# aa_battery_lado_a_lado.net
KiCad netlist of a schematic drawn in EAGLE
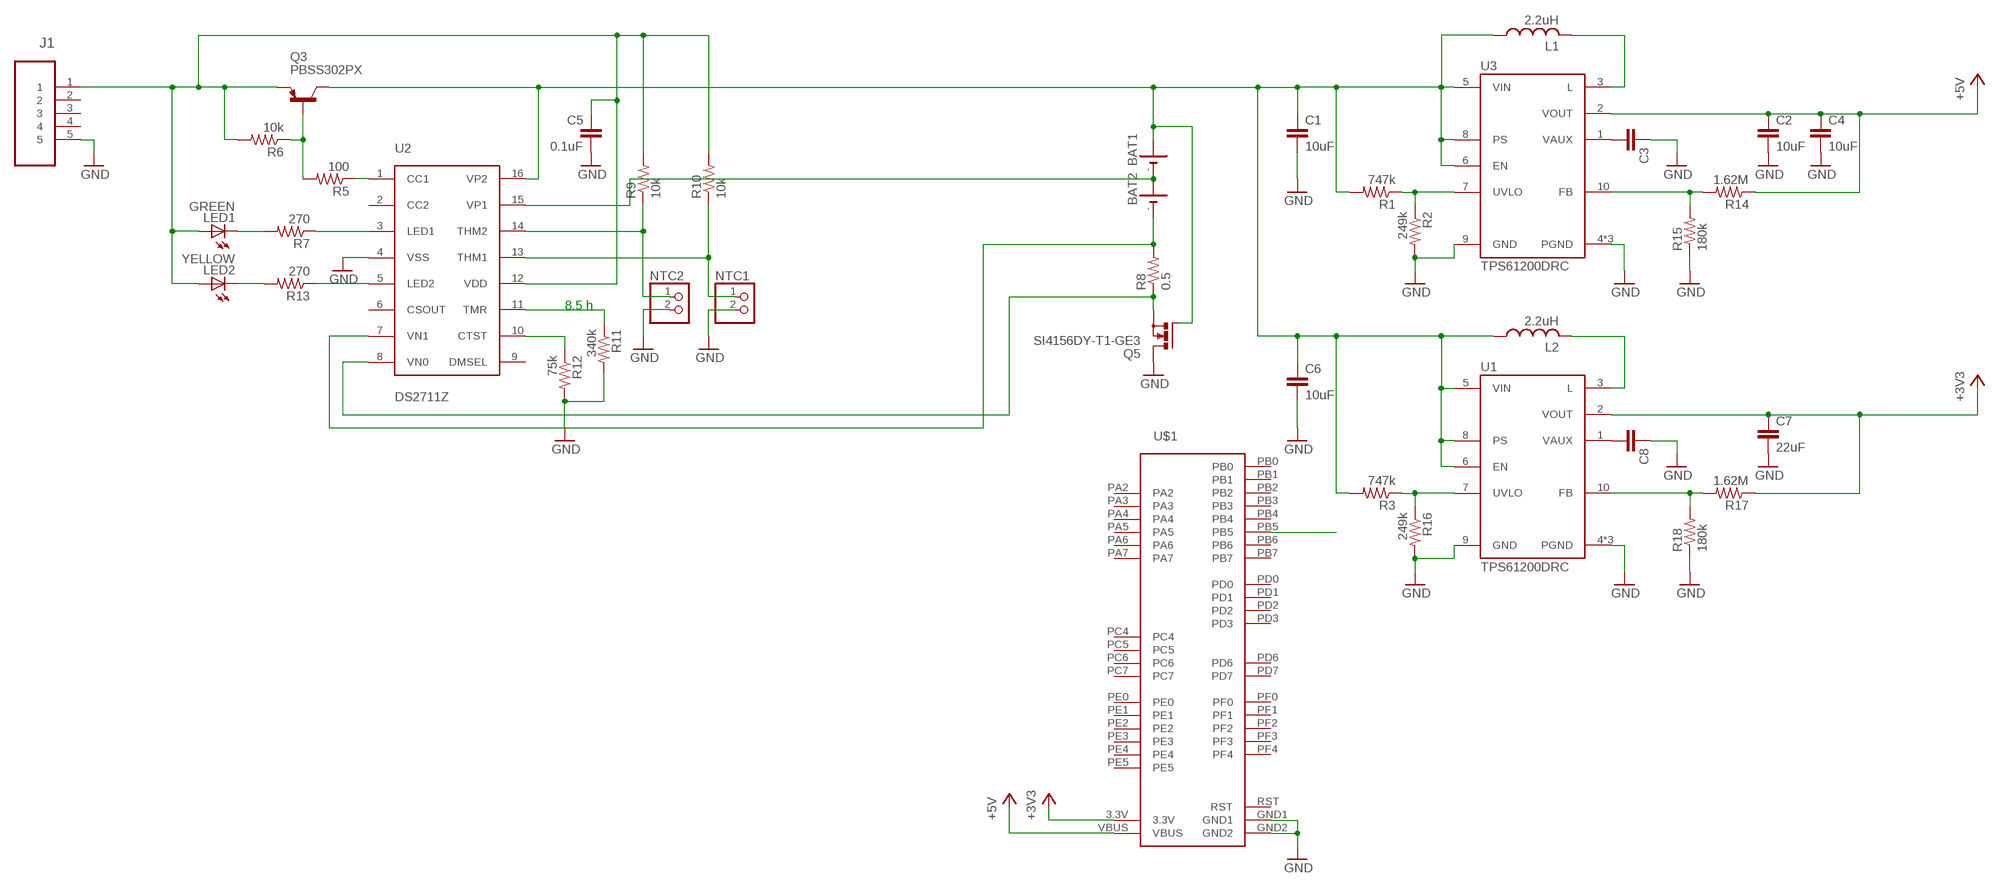
[diagram p0: schematic, sheet 1]

(export (version "E")
  (design (tool "Eeschema 10.0.6"))
  (components
    (comp (ref "BAT1")
      (value "AA-SNGLKEYSTONE2460")
      (footprint "eagle-import:KEYSTONE2460")
      (libsource (lib "eagle-import") (part "AA-SNGLKEYSTONE2460"))
    )
    (comp (ref "BAT2")
      (value "AA-SNGLKEYSTONE2460")
      (footprint "eagle-import:KEYSTONE2460")
      (libsource (lib "eagle-import") (part "AA-SNGLKEYSTONE2460"))
    )
    (comp (ref "C1")
      (value "10uF")
      (footprint "eagle-import:C0805")
      (libsource (lib "eagle-import") (part "C-EUC0805"))
    )
    (comp (ref "C2")
      (value "10uF")
      (footprint "eagle-import:C0805")
      (libsource (lib "eagle-import") (part "C-EUC0805"))
    )
    (comp (ref "C3")
      (value "C-EUC0805")
      (footprint "eagle-import:C0805")
      (libsource (lib "eagle-import") (part "C-EUC0805"))
    )
    (comp (ref "C4")
      (value "10uF")
      (footprint "eagle-import:C0805")
      (libsource (lib "eagle-import") (part "C-EUC0805"))
    )
    (comp (ref "C5")
      (value "0.1uF")
      (footprint "eagle-import:C0805")
      (libsource (lib "eagle-import") (part "C-EUC0805"))
    )
    (comp (ref "C6")
      (value "10uF")
      (footprint "eagle-import:C0805")
      (libsource (lib "eagle-import") (part "C-EUC0805"))
    )
    (comp (ref "C7")
      (value "22uF")
      (footprint "eagle-import:C0805")
      (libsource (lib "eagle-import") (part "C-EUC0805"))
    )
    (comp (ref "C8")
      (value "C-EUC0603")
      (footprint "eagle-import:C0603")
      (libsource (lib "eagle-import") (part "C-EUC0603"))
    )
    (comp (ref "J1")
      (value "47346-0001")
      (footprint "eagle-import:MOLEX_47346-0001")
      (libsource (lib "eagle-import") (part "47346-0001"))
    )
    (comp (ref "L1")
      (value "2.2uH")
      (footprint "eagle-import:XAL4040")
      (libsource (lib "eagle-import") (part "L-USXAL4040"))
    )
    (comp (ref "L2")
      (value "2.2uH")
      (footprint "eagle-import:XAL4040")
      (libsource (lib "eagle-import") (part "L-USXAL4040"))
    )
    (comp (ref "LED1")
      (value "GREEN")
      (footprint "eagle-import:SML1206")
      (libsource (lib "eagle-import") (part "LEDSML1206"))
    )
    (comp (ref "LED2")
      (value "YELLOW")
      (footprint "eagle-import:SML1206")
      (libsource (lib "eagle-import") (part "LEDSML1206"))
    )
    (comp (ref "NTC1")
      (value "PINHD-1X2")
      (footprint "eagle-import:1X02")
      (libsource (lib "eagle-import") (part "PINHD-1X2"))
    )
    (comp (ref "NTC2")
      (value "PINHD-1X2")
      (footprint "eagle-import:1X02")
      (libsource (lib "eagle-import") (part "PINHD-1X2"))
    )
    (comp (ref "Q3")
      (value "PBSS302PX")
      (footprint "eagle-import:SOT89-BCE")
      (libsource (lib "eagle-import") (part "-PNP-SOT98-BCEBF621"))
    )
    (comp (ref "Q5")
      (value "SI4156DY-T1-GE3")
      (footprint "eagle-import:SO-08")
      (libsource (lib "eagle-import") (part "N-MOSFET-SO8S"))
    )
    (comp (ref "R1")
      (value "747k")
      (footprint "eagle-import:R0603")
      (libsource (lib "eagle-import") (part "R-US_R0603"))
    )
    (comp (ref "R2")
      (value "249k")
      (footprint "eagle-import:R0603")
      (libsource (lib "eagle-import") (part "R-US_R0603"))
    )
    (comp (ref "R3")
      (value "747k")
      (footprint "eagle-import:R0603")
      (libsource (lib "eagle-import") (part "R-US_R0603"))
    )
    (comp (ref "R5")
      (value "100")
      (footprint "eagle-import:R0805")
      (libsource (lib "eagle-import") (part "R-US_R0805"))
    )
    (comp (ref "R6")
      (value "10k")
      (footprint "eagle-import:R0805")
      (libsource (lib "eagle-import") (part "R-US_R0805"))
    )
    (comp (ref "R7")
      (value "270")
      (footprint "eagle-import:R0805")
      (libsource (lib "eagle-import") (part "R-US_R0805"))
    )
    (comp (ref "R8")
      (value "0.5")
      (footprint "eagle-import:R0805")
      (libsource (lib "eagle-import") (part "R-US_R0805"))
    )
    (comp (ref "R9")
      (value "10k")
      (footprint "eagle-import:R0805")
      (libsource (lib "eagle-import") (part "R-US_R0805"))
    )
    (comp (ref "R10")
      (value "10k")
      (footprint "eagle-import:R0805")
      (libsource (lib "eagle-import") (part "R-US_R0805"))
    )
    (comp (ref "R11")
      (value "340k")
      (footprint "eagle-import:R0805")
      (libsource (lib "eagle-import") (part "R-US_R0805"))
    )
    (comp (ref "R12")
      (value "75k")
      (footprint "eagle-import:R0805")
      (libsource (lib "eagle-import") (part "R-US_R0805"))
    )
    (comp (ref "R13")
      (value "270")
      (footprint "eagle-import:R0805")
      (libsource (lib "eagle-import") (part "R-US_R0805"))
    )
    (comp (ref "R14")
      (value "1.62M")
      (footprint "eagle-import:R0603")
      (libsource (lib "eagle-import") (part "R-US_R0603"))
    )
    (comp (ref "R15")
      (value "180k")
      (footprint "eagle-import:R0603")
      (libsource (lib "eagle-import") (part "R-US_R0603"))
    )
    (comp (ref "R16")
      (value "249k")
      (footprint "eagle-import:R0603")
      (libsource (lib "eagle-import") (part "R-US_R0603"))
    )
    (comp (ref "R17")
      (value "1.62M")
      (footprint "eagle-import:R0603")
      (libsource (lib "eagle-import") (part "R-US_R0603"))
    )
    (comp (ref "R18")
      (value "180k")
      (footprint "eagle-import:R0603")
      (libsource (lib "eagle-import") (part "R-US_R0603"))
    )
    (comp (ref "U$1")
      (value "STELLARIS-LAUNCHPADSTELLARIS-LAUNCHPAD-XL-HALF-LENGTH")
      (footprint "eagle-import:LAUNCHPAD-XL-HALF-LENGTH")
      (libsource (lib "eagle-import") (part "STELLARIS-LAUNCHPADSTELLARIS-LAUNCHPAD-XL-HALF-LENGTH"))
    )
    (comp (ref "U1")
      (value "TPS61200DRC")
      (footprint "eagle-import:DRC10_2P4X1P65")
      (libsource (lib "eagle-import") (part "TPS61200DRC"))
    )
    (comp (ref "U2")
      (value "DS2711Z")
      (footprint "eagle-import:SO16")
      (libsource (lib "eagle-import") (part "DS2711Z"))
    )
    (comp (ref "U3")
      (value "TPS61200DRC")
      (footprint "eagle-import:DRC10_2P4X1P65")
      (libsource (lib "eagle-import") (part "TPS61200DRC"))
    )
  )
  (nets
    (net (code "1") (name "+3V3") (class "Default")
      (node (ref "C7") (pin "1") (pinfunction "1_1") (pintype "passive"))
      (node (ref "R17") (pin "1") (pinfunction "1_1") (pintype "passive"))
      (node (ref "U$1") (pin "3.3V") (pinfunction "3.3V_3.3V") (pintype "power_in"))
      (node (ref "U1") (pin "2") (pinfunction "VOUT_2") (pintype "bidirectional"))
    )
    (net (code "2") (name "+5V") (class "Default")
      (node (ref "C2") (pin "1") (pinfunction "1_1") (pintype "passive"))
      (node (ref "C4") (pin "1") (pinfunction "1_1") (pintype "passive"))
      (node (ref "R14") (pin "1") (pinfunction "1_1") (pintype "passive"))
      (node (ref "U$1") (pin "VBUS") (pinfunction "VBUS_VBUS") (pintype "power_in"))
      (node (ref "U3") (pin "2") (pinfunction "VOUT_2") (pintype "bidirectional"))
    )
    (net (code "3") (name "/RST") (class "Default")
      (node (ref "U$1") (pin "RST") (pinfunction "RST_RST") (pintype "power_in"))
    )
    (net (code "4") (name "GND") (class "Default")
      (node (ref "C1") (pin "2") (pinfunction "2_2") (pintype "passive"))
      (node (ref "C2") (pin "2") (pinfunction "2_2") (pintype "passive"))
      (node (ref "C3") (pin "1") (pinfunction "1_1") (pintype "passive"))
      (node (ref "C4") (pin "2") (pinfunction "2_2") (pintype "passive"))
      (node (ref "C5") (pin "2") (pinfunction "2_2") (pintype "passive"))
      (node (ref "C6") (pin "2") (pinfunction "2_2") (pintype "passive"))
      (node (ref "C7") (pin "2") (pinfunction "2_2") (pintype "passive"))
      (node (ref "C8") (pin "1") (pinfunction "1_1") (pintype "passive"))
      (node (ref "J1") (pin "5") (pinfunction "5_5") (pintype "input"))
      (node (ref "NTC1") (pin "2") (pinfunction "2_2") (pintype "passive"))
      (node (ref "NTC2") (pin "2") (pinfunction "2_2") (pintype "passive"))
      (node (ref "Q5") (pin "5") (pinfunction "D_5") (pintype "passive"))
      (node (ref "Q5") (pin "6") (pinfunction "D_6") (pintype "passive"))
      (node (ref "Q5") (pin "7") (pinfunction "D_7") (pintype "passive"))
      (node (ref "Q5") (pin "8") (pinfunction "D_8") (pintype "passive"))
      (node (ref "R11") (pin "2") (pinfunction "2_2") (pintype "passive"))
      (node (ref "R12") (pin "2") (pinfunction "2_2") (pintype "passive"))
      (node (ref "R15") (pin "1") (pinfunction "1_1") (pintype "passive"))
      (node (ref "R16") (pin "2") (pinfunction "2_2") (pintype "passive"))
      (node (ref "R18") (pin "1") (pinfunction "1_1") (pintype "passive"))
      (node (ref "R2") (pin "2") (pinfunction "2_2") (pintype "passive"))
      (node (ref "U$1") (pin "GND1") (pinfunction "GND1_GND1") (pintype "bidirectional"))
      (node (ref "U$1") (pin "GND2") (pinfunction "GND2_GND2") (pintype "power_in"))
      (node (ref "U1") (pin "11") (pinfunction "PGND_11") (pintype "bidirectional"))
      (node (ref "U1") (pin "12") (pinfunction "PGND_12") (pintype "bidirectional"))
      (node (ref "U1") (pin "4") (pinfunction "PGND_4") (pintype "bidirectional"))
      (node (ref "U1") (pin "9") (pinfunction "GND_9") (pintype "bidirectional"))
      (node (ref "U2") (pin "4") (pinfunction "VSS_4") (pintype "bidirectional"))
      (node (ref "U3") (pin "11") (pinfunction "PGND_11") (pintype "bidirectional"))
      (node (ref "U3") (pin "12") (pinfunction "PGND_12") (pintype "bidirectional"))
      (node (ref "U3") (pin "4") (pinfunction "PGND_4") (pintype "bidirectional"))
      (node (ref "U3") (pin "9") (pinfunction "GND_9") (pintype "bidirectional"))
    )
    (net (code "5") (name "Net-(LED1-PadC)") (class "Default")
      (node (ref "LED1") (pin "C") (pinfunction "C_C") (pintype "passive"))
      (node (ref "R7") (pin "2") (pinfunction "2_2") (pintype "passive"))
    )
    (net (code "6") (name "Net-(LED2-PadC)") (class "Default")
      (node (ref "LED2") (pin "C") (pinfunction "C_C") (pintype "passive"))
      (node (ref "R13") (pin "2") (pinfunction "2_2") (pintype "passive"))
    )
    (net (code "7") (name "Net-(Q3-PadB)") (class "Default")
      (node (ref "Q3") (pin "B") (pinfunction "B_B") (pintype "passive"))
      (node (ref "R5") (pin "2") (pinfunction "2_2") (pintype "passive"))
      (node (ref "R6") (pin "1") (pinfunction "1_1") (pintype "passive"))
    )
    (net (code "8") (name "Net-(Q5-G)") (class "Default")
      (node (ref "BAT1") (pin "+") (pinfunction "+_+") (pintype "passive"))
      (node (ref "C1") (pin "1") (pinfunction "1_1") (pintype "passive"))
      (node (ref "C6") (pin "1") (pinfunction "1_1") (pintype "passive"))
      (node (ref "L1") (pin "1") (pinfunction "1_1") (pintype "passive"))
      (node (ref "L2") (pin "1") (pinfunction "1_1") (pintype "passive"))
      (node (ref "Q3") (pin "C") (pinfunction "C_C") (pintype "passive"))
      (node (ref "Q3") (pin "C@1") (pinfunction "C_C@1") (pintype "passive"))
      (node (ref "Q5") (pin "4") (pinfunction "G_4") (pintype "passive"))
      (node (ref "R1") (pin "2") (pinfunction "2_2") (pintype "passive"))
      (node (ref "R3") (pin "2") (pinfunction "2_2") (pintype "passive"))
      (node (ref "U1") (pin "5") (pinfunction "VIN_5") (pintype "bidirectional"))
      (node (ref "U1") (pin "6") (pinfunction "EN_6") (pintype "bidirectional"))
      (node (ref "U1") (pin "8") (pinfunction "PS_8") (pintype "bidirectional"))
      (node (ref "U2") (pin "16") (pinfunction "VP2_16") (pintype "bidirectional"))
      (node (ref "U3") (pin "5") (pinfunction "VIN_5") (pintype "bidirectional"))
      (node (ref "U3") (pin "6") (pinfunction "EN_6") (pintype "bidirectional"))
      (node (ref "U3") (pin "8") (pinfunction "PS_8") (pintype "bidirectional"))
    )
    (net (code "9") (name "Net-(U1-FB)") (class "Default")
      (node (ref "R17") (pin "2") (pinfunction "2_2") (pintype "passive"))
      (node (ref "R18") (pin "2") (pinfunction "2_2") (pintype "passive"))
      (node (ref "U1") (pin "10") (pinfunction "FB_10") (pintype "bidirectional"))
    )
    (net (code "10") (name "Net-(U1-L)") (class "Default")
      (node (ref "L2") (pin "2") (pinfunction "2_2") (pintype "passive"))
      (node (ref "U1") (pin "3") (pinfunction "L_3") (pintype "bidirectional"))
    )
    (net (code "11") (name "Net-(U1-UVLO)") (class "Default")
      (node (ref "R16") (pin "1") (pinfunction "1_1") (pintype "passive"))
      (node (ref "R3") (pin "1") (pinfunction "1_1") (pintype "passive"))
      (node (ref "U1") (pin "7") (pinfunction "UVLO_7") (pintype "bidirectional"))
    )
    (net (code "12") (name "Net-(U1-VAUX)") (class "Default")
      (node (ref "C8") (pin "2") (pinfunction "2_2") (pintype "passive"))
      (node (ref "U1") (pin "1") (pinfunction "VAUX_1") (pintype "bidirectional"))
    )
    (net (code "13") (name "Net-(U2-CC1)") (class "Default")
      (node (ref "R5") (pin "1") (pinfunction "1_1") (pintype "passive"))
      (node (ref "U2") (pin "1") (pinfunction "CC1_1") (pintype "bidirectional"))
    )
    (net (code "14") (name "Net-(U2-CTST)") (class "Default")
      (node (ref "R12") (pin "1") (pinfunction "1_1") (pintype "passive"))
      (node (ref "U2") (pin "10") (pinfunction "CTST_10") (pintype "bidirectional"))
    )
    (net (code "15") (name "Net-(U2-LED1)") (class "Default")
      (node (ref "R7") (pin "1") (pinfunction "1_1") (pintype "passive"))
      (node (ref "U2") (pin "3") (pinfunction "LED1_3") (pintype "bidirectional"))
    )
    (net (code "16") (name "Net-(U2-LED2)") (class "Default")
      (node (ref "R13") (pin "1") (pinfunction "1_1") (pintype "passive"))
      (node (ref "U2") (pin "5") (pinfunction "LED2_5") (pintype "bidirectional"))
    )
    (net (code "17") (name "Net-(U2-THM1)") (class "Default")
      (node (ref "NTC1") (pin "1") (pinfunction "1_1") (pintype "passive"))
      (node (ref "R10") (pin "1") (pinfunction "1_1") (pintype "passive"))
      (node (ref "U2") (pin "13") (pinfunction "THM1_13") (pintype "bidirectional"))
    )
    (net (code "18") (name "Net-(U2-THM2)") (class "Default")
      (node (ref "NTC2") (pin "1") (pinfunction "1_1") (pintype "passive"))
      (node (ref "R9") (pin "1") (pinfunction "1_1") (pintype "passive"))
      (node (ref "U2") (pin "14") (pinfunction "THM2_14") (pintype "bidirectional"))
    )
    (net (code "19") (name "Net-(U2-TMR)") (class "Default")
      (node (ref "R11") (pin "1") (pinfunction "1_1") (pintype "passive"))
      (node (ref "U2") (pin "11") (pinfunction "TMR_11") (pintype "bidirectional"))
    )
    (net (code "20") (name "Net-(U2-VDD)") (class "Default")
      (node (ref "C5") (pin "1") (pinfunction "1_1") (pintype "passive"))
      (node (ref "J1") (pin "1") (pinfunction "1_1") (pintype "input"))
      (node (ref "LED1") (pin "A") (pinfunction "A_A") (pintype "passive"))
      (node (ref "LED2") (pin "A") (pinfunction "A_A") (pintype "passive"))
      (node (ref "Q3") (pin "E") (pinfunction "E_E") (pintype "passive"))
      (node (ref "R10") (pin "2") (pinfunction "2_2") (pintype "passive"))
      (node (ref "R6") (pin "2") (pinfunction "2_2") (pintype "passive"))
      (node (ref "R9") (pin "2") (pinfunction "2_2") (pintype "passive"))
      (node (ref "U2") (pin "12") (pinfunction "VDD_12") (pintype "bidirectional"))
    )
    (net (code "21") (name "Net-(U2-VN0)") (class "Default")
      (node (ref "Q5") (pin "1") (pinfunction "S_1") (pintype "passive"))
      (node (ref "Q5") (pin "2") (pinfunction "S_2") (pintype "passive"))
      (node (ref "Q5") (pin "3") (pinfunction "S_3") (pintype "passive"))
      (node (ref "R8") (pin "1") (pinfunction "1_1") (pintype "passive"))
      (node (ref "U2") (pin "8") (pinfunction "VN0_8") (pintype "bidirectional"))
    )
    (net (code "22") (name "Net-(U2-VN1)") (class "Default")
      (node (ref "BAT2") (pin "-") (pinfunction "-_-") (pintype "passive"))
      (node (ref "R8") (pin "2") (pinfunction "2_2") (pintype "passive"))
      (node (ref "U2") (pin "7") (pinfunction "VN1_7") (pintype "bidirectional"))
    )
    (net (code "23") (name "Net-(U2-VP1)") (class "Default")
      (node (ref "BAT1") (pin "-") (pinfunction "-_-") (pintype "passive"))
      (node (ref "BAT2") (pin "+") (pinfunction "+_+") (pintype "passive"))
      (node (ref "U2") (pin "15") (pinfunction "VP1_15") (pintype "bidirectional"))
    )
    (net (code "24") (name "Net-(U3-FB)") (class "Default")
      (node (ref "R14") (pin "2") (pinfunction "2_2") (pintype "passive"))
      (node (ref "R15") (pin "2") (pinfunction "2_2") (pintype "passive"))
      (node (ref "U3") (pin "10") (pinfunction "FB_10") (pintype "bidirectional"))
    )
    (net (code "25") (name "Net-(U3-L)") (class "Default")
      (node (ref "L1") (pin "2") (pinfunction "2_2") (pintype "passive"))
      (node (ref "U3") (pin "3") (pinfunction "L_3") (pintype "bidirectional"))
    )
    (net (code "26") (name "Net-(U3-UVLO)") (class "Default")
      (node (ref "R1") (pin "1") (pinfunction "1_1") (pintype "passive"))
      (node (ref "R2") (pin "1") (pinfunction "1_1") (pintype "passive"))
      (node (ref "U3") (pin "7") (pinfunction "UVLO_7") (pintype "bidirectional"))
    )
    (net (code "27") (name "Net-(U3-VAUX)") (class "Default")
      (node (ref "C3") (pin "2") (pinfunction "2_2") (pintype "passive"))
      (node (ref "U3") (pin "1") (pinfunction "VAUX_1") (pintype "bidirectional"))
    )
    (net (code "28") (name "unconnected-(J1-Pad2)") (class "Default")
      (node (ref "J1") (pin "2") (pinfunction "2_2") (pintype "input"))
    )
    (net (code "29") (name "unconnected-(J1-Pad3)") (class "Default")
      (node (ref "J1") (pin "3") (pinfunction "3_3") (pintype "input"))
    )
    (net (code "30") (name "unconnected-(J1-Pad4)") (class "Default")
      (node (ref "J1") (pin "4") (pinfunction "4_4") (pintype "input"))
    )
    (net (code "31") (name "unconnected-(U$1-PadPA2)") (class "Default")
      (node (ref "U$1") (pin "PA2") (pinfunction "PA2_PA2") (pintype "bidirectional"))
    )
    (net (code "32") (name "unconnected-(U$1-PadPA3)") (class "Default")
      (node (ref "U$1") (pin "PA3") (pinfunction "PA3_PA3") (pintype "bidirectional"))
    )
    (net (code "33") (name "unconnected-(U$1-PadPA4)") (class "Default")
      (node (ref "U$1") (pin "PA4") (pinfunction "PA4_PA4") (pintype "bidirectional"))
    )
    (net (code "34") (name "unconnected-(U$1-PadPA5)") (class "Default")
      (node (ref "U$1") (pin "PA5") (pinfunction "PA5_PA5") (pintype "bidirectional"))
    )
    (net (code "35") (name "unconnected-(U$1-PadPA6)") (class "Default")
      (node (ref "U$1") (pin "PA6") (pinfunction "PA6_PA6") (pintype "bidirectional"))
    )
    (net (code "36") (name "unconnected-(U$1-PadPA7)") (class "Default")
      (node (ref "U$1") (pin "PA7") (pinfunction "PA7_PA7") (pintype "bidirectional"))
    )
    (net (code "37") (name "unconnected-(U$1-PadPB0)") (class "Default")
      (node (ref "U$1") (pin "PB0") (pinfunction "PB0_PB0") (pintype "bidirectional"))
    )
    (net (code "38") (name "unconnected-(U$1-PadPB1)") (class "Default")
      (node (ref "U$1") (pin "PB1") (pinfunction "PB1_PB1") (pintype "bidirectional"))
    )
    (net (code "39") (name "unconnected-(U$1-PadPB2)") (class "Default")
      (node (ref "U$1") (pin "PB2") (pinfunction "PB2_PB2") (pintype "bidirectional"))
    )
    (net (code "40") (name "unconnected-(U$1-PadPB3)") (class "Default")
      (node (ref "U$1") (pin "PB3") (pinfunction "PB3_PB3") (pintype "bidirectional"))
    )
    (net (code "41") (name "unconnected-(U$1-PadPB4)") (class "Default")
      (node (ref "U$1") (pin "PB4") (pinfunction "PB4_PB4") (pintype "bidirectional"))
    )
    (net (code "42") (name "unconnected-(U$1-PadPB5)") (class "Default")
      (node (ref "U$1") (pin "PB5") (pinfunction "PB5_PB5") (pintype "bidirectional"))
    )
    (net (code "43") (name "unconnected-(U$1-PadPB6)") (class "Default")
      (node (ref "U$1") (pin "PB6") (pinfunction "PB6_PB6") (pintype "bidirectional"))
    )
    (net (code "44") (name "unconnected-(U$1-PadPB7)") (class "Default")
      (node (ref "U$1") (pin "PB7") (pinfunction "PB7_PB7") (pintype "bidirectional"))
    )
    (net (code "45") (name "unconnected-(U$1-PadPC4)") (class "Default")
      (node (ref "U$1") (pin "PC4") (pinfunction "PC4_PC4") (pintype "bidirectional"))
    )
    (net (code "46") (name "unconnected-(U$1-PadPC5)") (class "Default")
      (node (ref "U$1") (pin "PC5") (pinfunction "PC5_PC5") (pintype "bidirectional"))
    )
    (net (code "47") (name "unconnected-(U$1-PadPC6)") (class "Default")
      (node (ref "U$1") (pin "PC6") (pinfunction "PC6_PC6") (pintype "bidirectional"))
    )
    (net (code "48") (name "unconnected-(U$1-PadPC7)") (class "Default")
      (node (ref "U$1") (pin "PC7") (pinfunction "PC7_PC7") (pintype "bidirectional"))
    )
    (net (code "49") (name "unconnected-(U$1-PadPD0)") (class "Default")
      (node (ref "U$1") (pin "PD0") (pinfunction "PD0_PD0") (pintype "bidirectional"))
    )
    (net (code "50") (name "unconnected-(U$1-PadPD1)") (class "Default")
      (node (ref "U$1") (pin "PD1") (pinfunction "PD1_PD1") (pintype "bidirectional"))
    )
    (net (code "51") (name "unconnected-(U$1-PadPD2)") (class "Default")
      (node (ref "U$1") (pin "PD2") (pinfunction "PD2_PD2") (pintype "bidirectional"))
    )
    (net (code "52") (name "unconnected-(U$1-PadPD3)") (class "Default")
      (node (ref "U$1") (pin "PD3") (pinfunction "PD3_PD3") (pintype "bidirectional"))
    )
    (net (code "53") (name "unconnected-(U$1-PadPD6)") (class "Default")
      (node (ref "U$1") (pin "PD6") (pinfunction "PD6_PD6") (pintype "bidirectional"))
    )
    (net (code "54") (name "unconnected-(U$1-PadPD7)") (class "Default")
      (node (ref "U$1") (pin "PD7") (pinfunction "PD7_PD7") (pintype "bidirectional"))
    )
    (net (code "55") (name "unconnected-(U$1-PadPE0)") (class "Default")
      (node (ref "U$1") (pin "PE0") (pinfunction "PE0_PE0") (pintype "bidirectional"))
    )
    (net (code "56") (name "unconnected-(U$1-PadPE1)") (class "Default")
      (node (ref "U$1") (pin "PE1") (pinfunction "PE1_PE1") (pintype "bidirectional"))
    )
    (net (code "57") (name "unconnected-(U$1-PadPE2)") (class "Default")
      (node (ref "U$1") (pin "PE2") (pinfunction "PE2_PE2") (pintype "bidirectional"))
    )
    (net (code "58") (name "unconnected-(U$1-PadPE3)") (class "Default")
      (node (ref "U$1") (pin "PE3") (pinfunction "PE3_PE3") (pintype "bidirectional"))
    )
    (net (code "59") (name "unconnected-(U$1-PadPE4)") (class "Default")
      (node (ref "U$1") (pin "PE4") (pinfunction "PE4_PE4") (pintype "bidirectional"))
    )
    (net (code "60") (name "unconnected-(U$1-PadPE5)") (class "Default")
      (node (ref "U$1") (pin "PE5") (pinfunction "PE5_PE5") (pintype "bidirectional"))
    )
    (net (code "61") (name "unconnected-(U$1-PadPF0)") (class "Default")
      (node (ref "U$1") (pin "PF0") (pinfunction "PF0_PF0") (pintype "bidirectional"))
    )
    (net (code "62") (name "unconnected-(U$1-PadPF1)") (class "Default")
      (node (ref "U$1") (pin "PF1") (pinfunction "PF1_PF1") (pintype "bidirectional"))
    )
    (net (code "63") (name "unconnected-(U$1-PadPF2)") (class "Default")
      (node (ref "U$1") (pin "PF2") (pinfunction "PF2_PF2") (pintype "bidirectional"))
    )
    (net (code "64") (name "unconnected-(U$1-PadPF3)") (class "Default")
      (node (ref "U$1") (pin "PF3") (pinfunction "PF3_PF3") (pintype "bidirectional"))
    )
    (net (code "65") (name "unconnected-(U$1-PadPF4)") (class "Default")
      (node (ref "U$1") (pin "PF4") (pinfunction "PF4_PF4") (pintype "bidirectional"))
    )
    (net (code "66") (name "unconnected-(U2-CC2-Pad2)") (class "Default")
      (node (ref "U2") (pin "2") (pinfunction "CC2_2") (pintype "bidirectional"))
    )
    (net (code "67") (name "unconnected-(U2-CSOUT-Pad6)") (class "Default")
      (node (ref "U2") (pin "6") (pinfunction "CSOUT_6") (pintype "bidirectional"))
    )
    (net (code "68") (name "unconnected-(U2-DMSEL-Pad9)") (class "Default")
      (node (ref "U2") (pin "9") (pinfunction "DMSEL_9") (pintype "bidirectional"))
    )
  )
)
